# 1V8_SUPPLY.net
KiCad netlist of a schematic drawn in Altium Designer
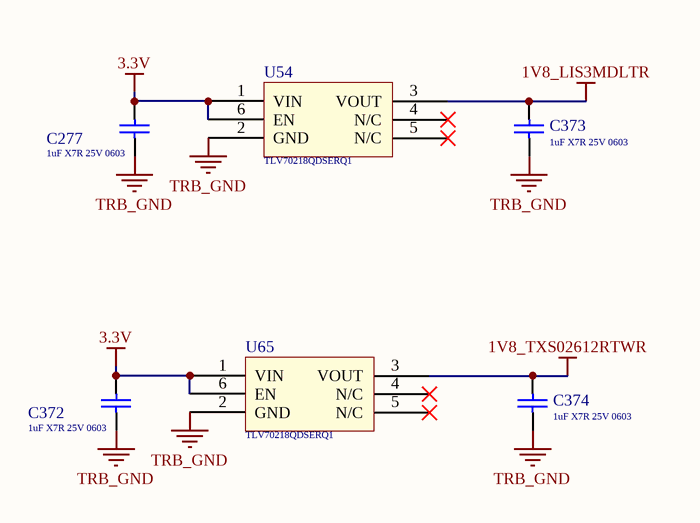
[diagram p0: 1V8_SUPPLY.SchDoc]

(export (version "E")
  (design (tool "Eeschema 10.0.6"))
  (components
    (comp (ref "C277")
      (value "Cap_Murata_GCJ188R71E105KA01J_1uF")
      (footprint "Cap_Murata_GCJ188R71E105KA01J_1uF")
      (description "CAP CER 1uF 25V X7R 0603")
      (fields (field (name "CAPACITANCE") "1uF X7R 25V 0603"))
      (libsource (lib "Cap_Murata_GCJ188R71E105KA01J_1uF") (part "Cap_Murata_GCJ188R71E105KA01J_1uF"))
    )
    (comp (ref "C372")
      (value "Cap_Murata_GCJ188R71E105KA01J_1uF")
      (footprint "Cap_Murata_GCJ188R71E105KA01J_1uF")
      (description "CAP CER 1uF 25V X7R 0603")
      (fields (field (name "CAPACITANCE") "1uF X7R 25V 0603"))
      (libsource (lib "Cap_Murata_GCJ188R71E105KA01J_1uF") (part "Cap_Murata_GCJ188R71E105KA01J_1uF"))
    )
    (comp (ref "C373")
      (value "Cap_Murata_GCJ188R71E105KA01J_1uF")
      (footprint "Cap_Murata_GCJ188R71E105KA01J_1uF")
      (description "CAP CER 1uF 25V X7R 0603")
      (fields (field (name "CAPACITANCE") "1uF X7R 25V 0603"))
      (libsource (lib "Cap_Murata_GCJ188R71E105KA01J_1uF") (part "Cap_Murata_GCJ188R71E105KA01J_1uF"))
    )
    (comp (ref "C374")
      (value "Cap_Murata_GCJ188R71E105KA01J_1uF")
      (footprint "Cap_Murata_GCJ188R71E105KA01J_1uF")
      (description "CAP CER 1uF 25V X7R 0603")
      (fields (field (name "CAPACITANCE") "1uF X7R 25V 0603"))
      (libsource (lib "Cap_Murata_GCJ188R71E105KA01J_1uF") (part "Cap_Murata_GCJ188R71E105KA01J_1uF"))
    )
    (comp (ref "U54")
      (value "LDO_Texas_Instruments_TLV70218QDSERQ1_300mA")
      (footprint "LDO_Texas_Instruments_TLV70218QDSERQ1_300mA")
      (description "LDO Voltage Regulators 300mA Low")
      (fields (field (name "SERIES") "TLV70218QDSERQ1"))
      (libsource (lib "LDO_Texas_Instruments_TLV70218QDSERQ1_300mA") (part "LDO_Texas_Instruments_TLV70218QDSERQ1_300mA"))
    )
    (comp (ref "U65")
      (value "LDO_Texas_Instruments_TLV70218QDSERQ1_300mA")
      (footprint "LDO_Texas_Instruments_TLV70218QDSERQ1_300mA")
      (description "LDO Voltage Regulators 300mA Low")
      (fields (field (name "SERIES") "TLV70218QDSERQ1"))
      (libsource (lib "LDO_Texas_Instruments_TLV70218QDSERQ1_300mA") (part "LDO_Texas_Instruments_TLV70218QDSERQ1_300mA"))
    )
  )
  (nets
    (net (code "1") (name "1V8_LIS3MDLTR") (class "Default")
      (node (ref "C373") (pin "2") (pinfunction "2_2") (pintype "passive"))
      (node (ref "U54") (pin "3") (pinfunction "VOUT_3") (pintype "passive"))
    )
    (net (code "2") (name "1V8_TXS02612RTWR") (class "Default")
      (node (ref "C374") (pin "2") (pinfunction "2_2") (pintype "passive"))
      (node (ref "U65") (pin "3") (pinfunction "VOUT_3") (pintype "passive"))
    )
    (net (code "3") (name "3.3V") (class "Default")
      (node (ref "C277") (pin "2") (pinfunction "2_2") (pintype "passive"))
      (node (ref "C372") (pin "2") (pinfunction "2_2") (pintype "passive"))
      (node (ref "U54") (pin "1") (pinfunction "VIN_1") (pintype "passive"))
      (node (ref "U54") (pin "6") (pinfunction "EN_6") (pintype "passive"))
      (node (ref "U65") (pin "1") (pinfunction "VIN_1") (pintype "passive"))
      (node (ref "U65") (pin "6") (pinfunction "EN_6") (pintype "passive"))
    )
    (net (code "4") (name "TRB_GND") (class "Default")
      (node (ref "C277") (pin "1") (pinfunction "1_1") (pintype "passive"))
      (node (ref "C372") (pin "1") (pinfunction "1_1") (pintype "passive"))
      (node (ref "C373") (pin "1") (pinfunction "1_1") (pintype "passive"))
      (node (ref "C374") (pin "1") (pinfunction "1_1") (pintype "passive"))
      (node (ref "U54") (pin "2") (pinfunction "GND_2") (pintype "passive"))
      (node (ref "U65") (pin "2") (pinfunction "GND_2") (pintype "passive"))
    )
    (net (code "5") (name "unconnected-(U54-N{slash}C-Pad4)") (class "Default")
      (node (ref "U54") (pin "4") (pinfunction "N/C_4") (pintype "passive+no_connect"))
    )
    (net (code "6") (name "unconnected-(U54-N{slash}C-Pad5)") (class "Default")
      (node (ref "U54") (pin "5") (pinfunction "N/C_5") (pintype "passive+no_connect"))
    )
    (net (code "7") (name "unconnected-(U65-N{slash}C-Pad4)") (class "Default")
      (node (ref "U65") (pin "4") (pinfunction "N/C_4") (pintype "passive+no_connect"))
    )
    (net (code "8") (name "unconnected-(U65-N{slash}C-Pad5)") (class "Default")
      (node (ref "U65") (pin "5") (pinfunction "N/C_5") (pintype "passive+no_connect"))
    )
  )
)
